# Pir-RElay.net
KiCad netlist of a schematic drawn in EAGLE
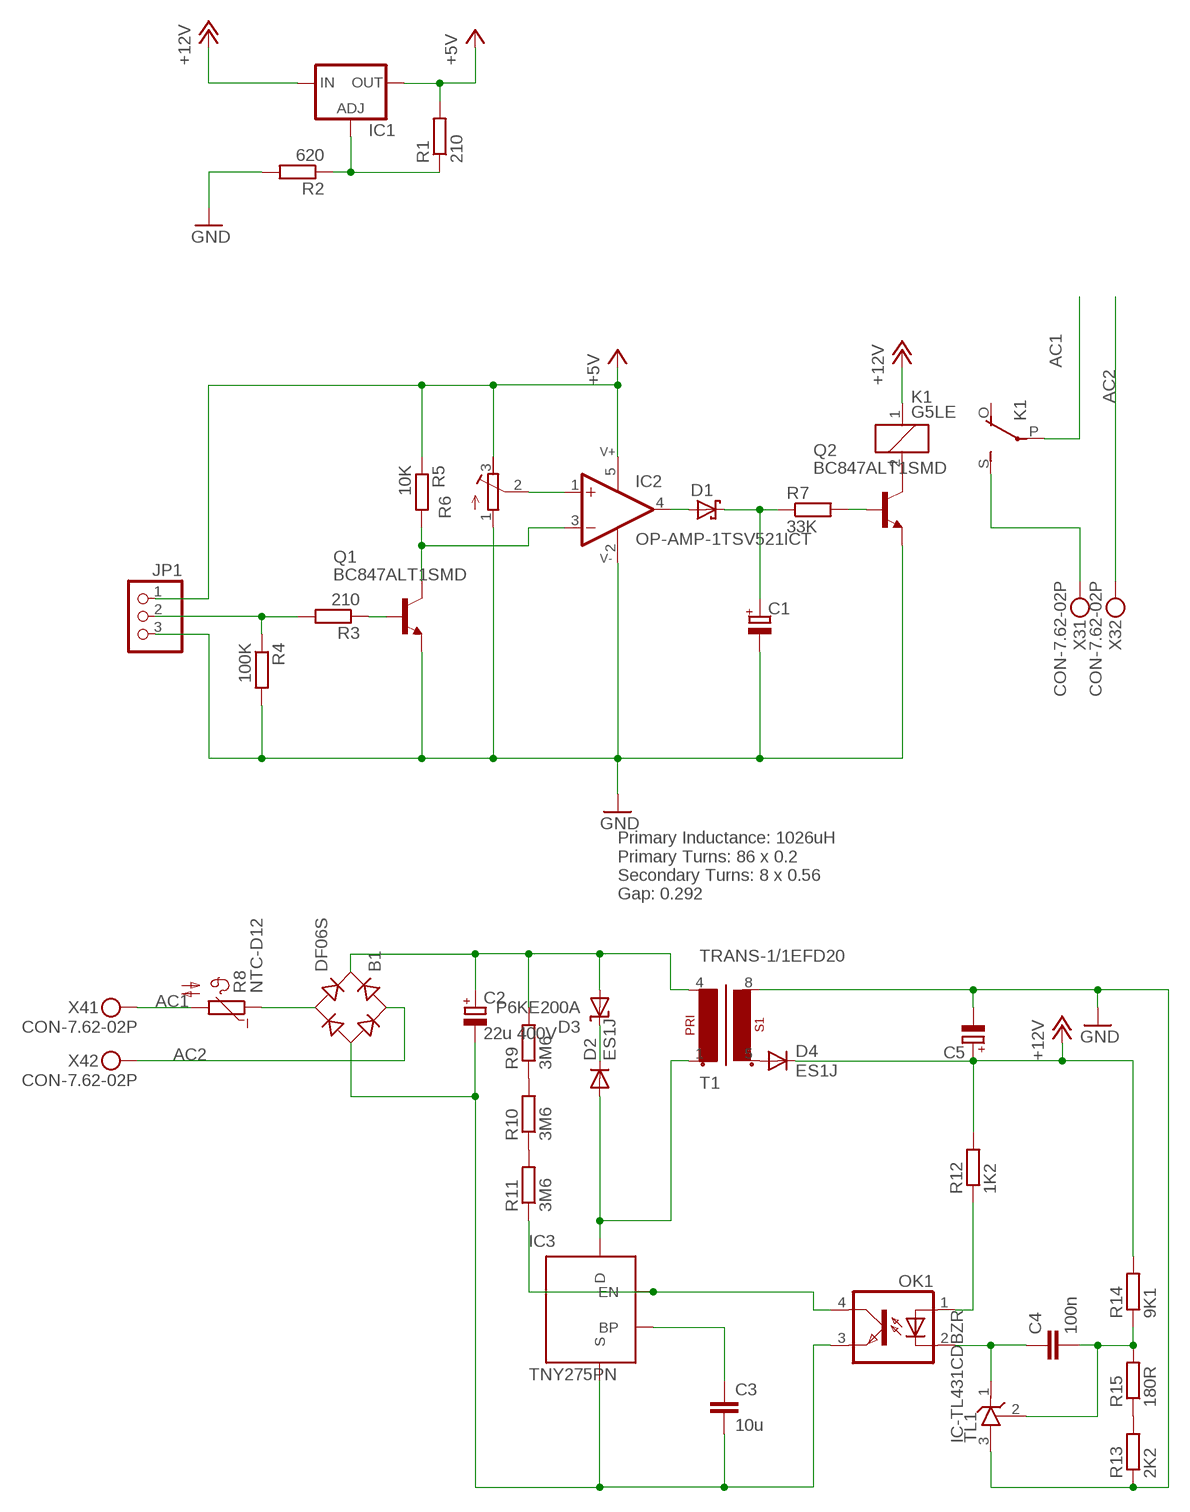
[diagram p0: schematic, sheet 1]

(export (version "E")
  (design (tool "Eeschema 10.0.6"))
  (components
    (comp (ref "B1")
      (value "DF06S")
      (footprint "eagle-import:DFS")
      (libsource (lib "eagle-import") (part "DFS06"))
    )
    (comp (ref "C1")
      (value "CAP-POL_E2.5-7")
      (footprint "eagle-import:E2,5-7")
      (libsource (lib "eagle-import") (part "CAP-POL_E2.5-7"))
    )
    (comp (ref "C2")
      (value "22u 400V")
      (footprint "eagle-import:E5-13")
      (libsource (lib "eagle-import") (part "CPOL-EUE5-13"))
    )
    (comp (ref "C3")
      (value "10u")
      (footprint "eagle-import:C1210")
      (libsource (lib "eagle-import") (part "CAP_1210"))
    )
    (comp (ref "C4")
      (value "100n")
      (footprint "eagle-import:C0805")
      (libsource (lib "eagle-import") (part "CAP_0805"))
    )
    (comp (ref "C5")
      (value "CPOL-EUE7.5-18")
      (footprint "eagle-import:E7,5-18")
      (libsource (lib "eagle-import") (part "CPOL-EUE7.5-18"))
    )
    (comp (ref "D1")
      (value "DIODE-SH_SOD523")
      (footprint "eagle-import:SODFL1608X65")
      (libsource (lib "eagle-import") (part "DIODE-SH_SOD523"))
    )
    (comp (ref "D2")
      (value "ES1J")
      (footprint "eagle-import:DO214AC")
      (libsource (lib "eagle-import") (part "DIODE_ES1J"))
    )
    (comp (ref "D3")
      (value "P6KE200A")
      (footprint "eagle-import:DO15-12")
      (libsource (lib "eagle-import") (part "SUPRESSORDO-204AC"))
    )
    (comp (ref "D4")
      (value "ES1J")
      (footprint "eagle-import:DO214AC")
      (libsource (lib "eagle-import") (part "DIODE_ES1J"))
    )
    (comp (ref "IC1")
      (value "VREG-ADJLD1117S")
      (footprint "eagle-import:SOT230P700X180-4")
      (libsource (lib "eagle-import") (part "VREG-ADJLD1117S"))
    )
    (comp (ref "IC2")
      (value "OP-AMP-1TSV521ICT")
      (footprint "eagle-import:SC70-5L")
      (libsource (lib "eagle-import") (part "OP-AMP-1TSV521ICT"))
    )
    (comp (ref "IC3")
      (value "TNY275PN")
      (footprint "eagle-import:DIP-8C")
      (libsource (lib "eagle-import") (part "POWER-TNY275"))
    )
    (comp (ref "JP1")
      (value "PINHD-1X3/90")
      (footprint "eagle-import:1X03_90")
      (libsource (lib "eagle-import") (part "PINHD-1X3/90"))
    )
    (comp (ref "K1")
      (value "G5LE")
      (footprint "eagle-import:G5LE")
      (libsource (lib "eagle-import") (part "G5LE"))
    )
    (comp (ref "OK1")
      (value "OPTOTRANSPC817")
      (footprint "eagle-import:DIL04")
      (fields (field (name "MPN") "PC817X4J000F"))
      (libsource (lib "eagle-import") (part "OPTOTRANSPC817"))
    )
    (comp (ref "Q1")
      (value "BC847ALT1SMD")
      (footprint "eagle-import:SOT23")
      (libsource (lib "eagle-import") (part "BC847SMDALT1"))
    )
    (comp (ref "Q2")
      (value "BC847ALT1SMD")
      (footprint "eagle-import:SOT23")
      (libsource (lib "eagle-import") (part "BC847SMDALT1"))
    )
    (comp (ref "R1")
      (value "210")
      (footprint "eagle-import:RESC2012X50")
      (libsource (lib "eagle-import") (part "R_R0805"))
    )
    (comp (ref "R2")
      (value "620")
      (footprint "eagle-import:RESC2012X50")
      (libsource (lib "eagle-import") (part "R_R0805"))
    )
    (comp (ref "R3")
      (value "210")
      (footprint "eagle-import:RESC2012X50")
      (libsource (lib "eagle-import") (part "R_R0805"))
    )
    (comp (ref "R4")
      (value "100K")
      (footprint "eagle-import:RESC2012X50")
      (libsource (lib "eagle-import") (part "R_R0805"))
    )
    (comp (ref "R5")
      (value "10K")
      (footprint "eagle-import:RESC2012X50")
      (libsource (lib "eagle-import") (part "R_R0805"))
    )
    (comp (ref "R6")
      (value "R_POT3296X")
      (footprint "eagle-import:POT-3296X")
      (libsource (lib "eagle-import") (part "R_POT3296X"))
    )
    (comp (ref "R7")
      (value "33K")
      (footprint "eagle-import:RESC2012X50")
      (libsource (lib "eagle-import") (part "R_R0805"))
    )
    (comp (ref "R8")
      (value "NTC-D12")
      (footprint "eagle-import:NTC-D12")
      (libsource (lib "eagle-import") (part "NTC-D12"))
    )
    (comp (ref "R9")
      (value "3M6")
      (footprint "eagle-import:R0805")
      (libsource (lib "eagle-import") (part "R_0805"))
    )
    (comp (ref "R10")
      (value "3M6")
      (footprint "eagle-import:R0805")
      (libsource (lib "eagle-import") (part "R_0805"))
    )
    (comp (ref "R11")
      (value "3M6")
      (footprint "eagle-import:R0805")
      (libsource (lib "eagle-import") (part "R_0805"))
    )
    (comp (ref "R12")
      (value "1K2")
      (footprint "eagle-import:R1206")
      (libsource (lib "eagle-import") (part "R_1206"))
    )
    (comp (ref "R13")
      (value "2K2")
      (footprint "eagle-import:RESC2012X50")
      (libsource (lib "eagle-import") (part "R_R0805"))
    )
    (comp (ref "R14")
      (value "9K1")
      (footprint "eagle-import:R1206")
      (libsource (lib "eagle-import") (part "R_1206"))
    )
    (comp (ref "R15")
      (value "180R")
      (footprint "eagle-import:R1206")
      (libsource (lib "eagle-import") (part "R_1206"))
    )
    (comp (ref "T1")
      (value "TRANS-1/1EFD20")
      (footprint "eagle-import:EFD20_8PIN")
      (libsource (lib "eagle-import") (part "TRANS-1/1EFD20"))
    )
    (comp (ref "TL1")
      (value "IC-TL431CDBZR")
      (footprint "eagle-import:SOT23")
      (libsource (lib "eagle-import") (part "IC-TL431CDBZR"))
    )
    (comp (ref "X3")
      (value "CON-7.62-02P")
      (footprint "eagle-import:KF25C-7.62-02P-13")
      (libsource (lib "eagle-import") (part "CON-7.62-02P"))
    )
    (comp (ref "X4")
      (value "CON-7.62-02P")
      (footprint "eagle-import:KF25C-7.62-02P-13")
      (libsource (lib "eagle-import") (part "CON-7.62-02P"))
    )
  )
  (nets
    (net (code "1") (name "+5V") (class "Default")
      (node (ref "IC1") (pin "2") (pinfunction "OUT_2") (pintype "passive"))
      (node (ref "IC1") (pin "4") (pinfunction "OUT_4") (pintype "passive"))
      (node (ref "IC2") (pin "5") (pinfunction "V+_5") (pintype "power_in"))
      (node (ref "JP1") (pin "1") (pinfunction "1_1") (pintype "passive"))
      (node (ref "R1") (pin "2") (pinfunction "2_2") (pintype "passive"))
      (node (ref "R5") (pin "1") (pinfunction "1_1") (pintype "passive"))
      (node (ref "R6") (pin "3") (pinfunction "E_3") (pintype "passive"))
    )
    (net (code "2") (name "+12V") (class "Default")
      (node (ref "C5") (pin "+") (pinfunction "+_+") (pintype "passive"))
      (node (ref "D4") (pin "C") (pinfunction "C_C") (pintype "passive"))
      (node (ref "IC1") (pin "3") (pinfunction "IN_3") (pintype "input"))
      (node (ref "K1") (pin "1") (pinfunction "1_1") (pintype "passive"))
      (node (ref "R12") (pin "2") (pinfunction "2_2") (pintype "passive"))
      (node (ref "R14") (pin "2") (pinfunction "2_2") (pintype "passive"))
    )
    (net (code "3") (name "/AC1") (class "Default")
      (node (ref "K1") (pin "P") (pinfunction "P_P") (pintype "passive"))
      (node (ref "R8") (pin "2") (pinfunction "2_2") (pintype "passive"))
      (node (ref "X4") (pin "P$1") (pinfunction "KL_P$1") (pintype "passive"))
    )
    (net (code "4") (name "/AC2") (class "Default")
      (node (ref "B1") (pin "AC1") (pinfunction "AC1_AC1") (pintype "passive"))
      (node (ref "X3") (pin "P$2") (pinfunction "KL_P$2") (pintype "passive"))
      (node (ref "X4") (pin "P$2") (pinfunction "KL_P$2") (pintype "passive"))
    )
    (net (code "5") (name "GND") (class "Default")
      (node (ref "C1") (pin "-") (pinfunction "-_-") (pintype "passive"))
      (node (ref "C5") (pin "-") (pinfunction "-_-") (pintype "passive"))
      (node (ref "IC2") (pin "2") (pinfunction "V-_2") (pintype "power_in"))
      (node (ref "JP1") (pin "3") (pinfunction "3_3") (pintype "passive"))
      (node (ref "Q1") (pin "2") (pinfunction "E_2") (pintype "passive"))
      (node (ref "Q2") (pin "2") (pinfunction "E_2") (pintype "passive"))
      (node (ref "R13") (pin "1") (pinfunction "1_1") (pintype "passive"))
      (node (ref "R2") (pin "2") (pinfunction "2_2") (pintype "passive"))
      (node (ref "R4") (pin "2") (pinfunction "2_2") (pintype "passive"))
      (node (ref "R6") (pin "1") (pinfunction "A_1") (pintype "passive"))
      (node (ref "T1") (pin "8") (pinfunction "S1-2_8") (pintype "passive"))
      (node (ref "TL1") (pin "3") (pinfunction "A_3") (pintype "passive"))
    )
    (net (code "6") (name "Net-(B1-PadAC2)") (class "Default")
      (node (ref "B1") (pin "AC2") (pinfunction "AC2_AC2") (pintype "passive"))
      (node (ref "R8") (pin "1") (pinfunction "1_1") (pintype "passive"))
    )
    (net (code "7") (name "Net-(D1-A)") (class "Default")
      (node (ref "D1") (pin "2") (pinfunction "A_2") (pintype "passive"))
      (node (ref "IC2") (pin "4") (pinfunction "OUT_4") (pintype "output"))
    )
    (net (code "8") (name "Net-(D1-C)") (class "Default")
      (node (ref "C1") (pin "+") (pinfunction "+_+") (pintype "passive"))
      (node (ref "D1") (pin "1") (pinfunction "C_1") (pintype "passive"))
      (node (ref "R7") (pin "1") (pinfunction "1_1") (pintype "passive"))
    )
    (net (code "9") (name "Net-(D2-PadC)") (class "Default")
      (node (ref "D2") (pin "C") (pinfunction "C_C") (pintype "passive"))
      (node (ref "D3") (pin "C") (pinfunction "C_C") (pintype "passive"))
    )
    (net (code "10") (name "Net-(IC1-ADJ)") (class "Default")
      (node (ref "IC1") (pin "1") (pinfunction "ADJ_1") (pintype "input"))
      (node (ref "R1") (pin "1") (pinfunction "1_1") (pintype "passive"))
      (node (ref "R2") (pin "1") (pinfunction "1_1") (pintype "passive"))
    )
    (net (code "11") (name "Net-(IC2A-+IN)") (class "Default")
      (node (ref "IC2") (pin "1") (pinfunction "+IN_1") (pintype "input"))
      (node (ref "R6") (pin "2") (pinfunction "S_2") (pintype "passive"))
    )
    (net (code "12") (name "Net-(IC2A--IN)") (class "Default")
      (node (ref "IC2") (pin "3") (pinfunction "-IN_3") (pintype "input"))
      (node (ref "Q1") (pin "3") (pinfunction "C_3") (pintype "passive"))
      (node (ref "R5") (pin "2") (pinfunction "2_2") (pintype "passive"))
    )
    (net (code "13") (name "Net-(IC3-BP)") (class "Default")
      (node (ref "C3") (pin "1") (pinfunction "1_1") (pintype "passive"))
      (node (ref "IC3") (pin "2") (pinfunction "BP_2") (pintype "input"))
    )
    (net (code "14") (name "Net-(IC3-D)") (class "Default")
      (node (ref "D2") (pin "A") (pinfunction "A_A") (pintype "passive"))
      (node (ref "IC3") (pin "4") (pinfunction "D_4") (pintype "input"))
      (node (ref "T1") (pin "1") (pinfunction "P1-1_1") (pintype "passive"))
    )
    (net (code "15") (name "Net-(IC3-EN)") (class "Default")
      (node (ref "IC3") (pin "1") (pinfunction "EN_1") (pintype "input"))
      (node (ref "OK1") (pin "4") (pinfunction "COL_4") (pintype "passive"))
      (node (ref "R11") (pin "1") (pinfunction "1_1") (pintype "passive"))
    )
    (net (code "16") (name "Net-(JP1-Pad2)") (class "Default")
      (node (ref "JP1") (pin "2") (pinfunction "2_2") (pintype "passive"))
      (node (ref "R3") (pin "2") (pinfunction "2_2") (pintype "passive"))
      (node (ref "R4") (pin "1") (pinfunction "1_1") (pintype "passive"))
    )
    (net (code "17") (name "Net-(OK1-A)") (class "Default")
      (node (ref "OK1") (pin "1") (pinfunction "A_1") (pintype "passive"))
      (node (ref "R12") (pin "1") (pinfunction "1_1") (pintype "passive"))
    )
    (net (code "18") (name "Net-(OK1-C)") (class "Default")
      (node (ref "C4") (pin "1") (pinfunction "1_1") (pintype "passive"))
      (node (ref "OK1") (pin "2") (pinfunction "C_2") (pintype "passive"))
      (node (ref "TL1") (pin "1") (pinfunction "C_1") (pintype "passive"))
    )
    (net (code "19") (name "Net-(OK1-EMIT)") (class "Default")
      (node (ref "B1") (pin "-") (pinfunction "-_-") (pintype "passive"))
      (node (ref "C2") (pin "-") (pinfunction "-_-") (pintype "passive"))
      (node (ref "C3") (pin "2") (pinfunction "2_2") (pintype "passive"))
      (node (ref "IC3") (pin "5") (pinfunction "S_5") (pintype "input"))
      (node (ref "IC3") (pin "6") (pinfunction "S_6") (pintype "input"))
      (node (ref "IC3") (pin "7") (pinfunction "S_7") (pintype "input"))
      (node (ref "IC3") (pin "8") (pinfunction "S_8") (pintype "input"))
      (node (ref "OK1") (pin "3") (pinfunction "EMIT_3") (pintype "passive"))
    )
    (net (code "20") (name "Net-(Q1-B)") (class "Default")
      (node (ref "Q1") (pin "1") (pinfunction "B_1") (pintype "passive"))
      (node (ref "R3") (pin "1") (pinfunction "1_1") (pintype "passive"))
    )
    (net (code "21") (name "Net-(Q2-B)") (class "Default")
      (node (ref "Q2") (pin "1") (pinfunction "B_1") (pintype "passive"))
      (node (ref "R7") (pin "2") (pinfunction "2_2") (pintype "passive"))
    )
    (net (code "22") (name "Net-(Q2-C)") (class "Default")
      (node (ref "K1") (pin "2") (pinfunction "2_2") (pintype "passive"))
      (node (ref "Q2") (pin "3") (pinfunction "C_3") (pintype "passive"))
    )
    (net (code "23") (name "Net-(R10-Pad1)") (class "Default")
      (node (ref "R10") (pin "1") (pinfunction "1_1") (pintype "passive"))
      (node (ref "R11") (pin "2") (pinfunction "2_2") (pintype "passive"))
    )
    (net (code "24") (name "Net-(R10-Pad2)") (class "Default")
      (node (ref "R10") (pin "2") (pinfunction "2_2") (pintype "passive"))
      (node (ref "R9") (pin "1") (pinfunction "1_1") (pintype "passive"))
    )
    (net (code "25") (name "Net-(R13-Pad2)") (class "Default")
      (node (ref "R13") (pin "2") (pinfunction "2_2") (pintype "passive"))
      (node (ref "R15") (pin "1") (pinfunction "1_1") (pintype "passive"))
    )
    (net (code "26") (name "Net-(T1-P1-2)") (class "Default")
      (node (ref "B1") (pin "+") (pinfunction "+_+") (pintype "passive"))
      (node (ref "C2") (pin "+") (pinfunction "+_+") (pintype "passive"))
      (node (ref "D3") (pin "A") (pinfunction "A_A") (pintype "passive"))
      (node (ref "R9") (pin "2") (pinfunction "2_2") (pintype "passive"))
      (node (ref "T1") (pin "4") (pinfunction "P1-2_4") (pintype "passive"))
    )
    (net (code "27") (name "Net-(T1-S1-1)") (class "Default")
      (node (ref "D4") (pin "A") (pinfunction "A_A") (pintype "passive"))
      (node (ref "T1") (pin "5") (pinfunction "S1-1_5") (pintype "passive"))
    )
    (net (code "28") (name "Net-(TL1-R)") (class "Default")
      (node (ref "C4") (pin "2") (pinfunction "2_2") (pintype "passive"))
      (node (ref "R14") (pin "1") (pinfunction "1_1") (pintype "passive"))
      (node (ref "R15") (pin "2") (pinfunction "2_2") (pintype "passive"))
      (node (ref "TL1") (pin "2") (pinfunction "R_2") (pintype "passive"))
    )
    (net (code "29") (name "Net-(X3A-KL)") (class "Default")
      (node (ref "K1") (pin "S") (pinfunction "S_S") (pintype "passive"))
      (node (ref "X3") (pin "P$1") (pinfunction "KL_P$1") (pintype "passive"))
    )
    (net (code "30") (name "unconnected-(K1-PadO)") (class "Default")
      (node (ref "K1") (pin "O") (pinfunction "O_O") (pintype "passive"))
    )
  )
)
